# SCH_CubeSat_Arduino__2024-08-11.net
KiCad netlist of a schematic drawn in EasyEDA
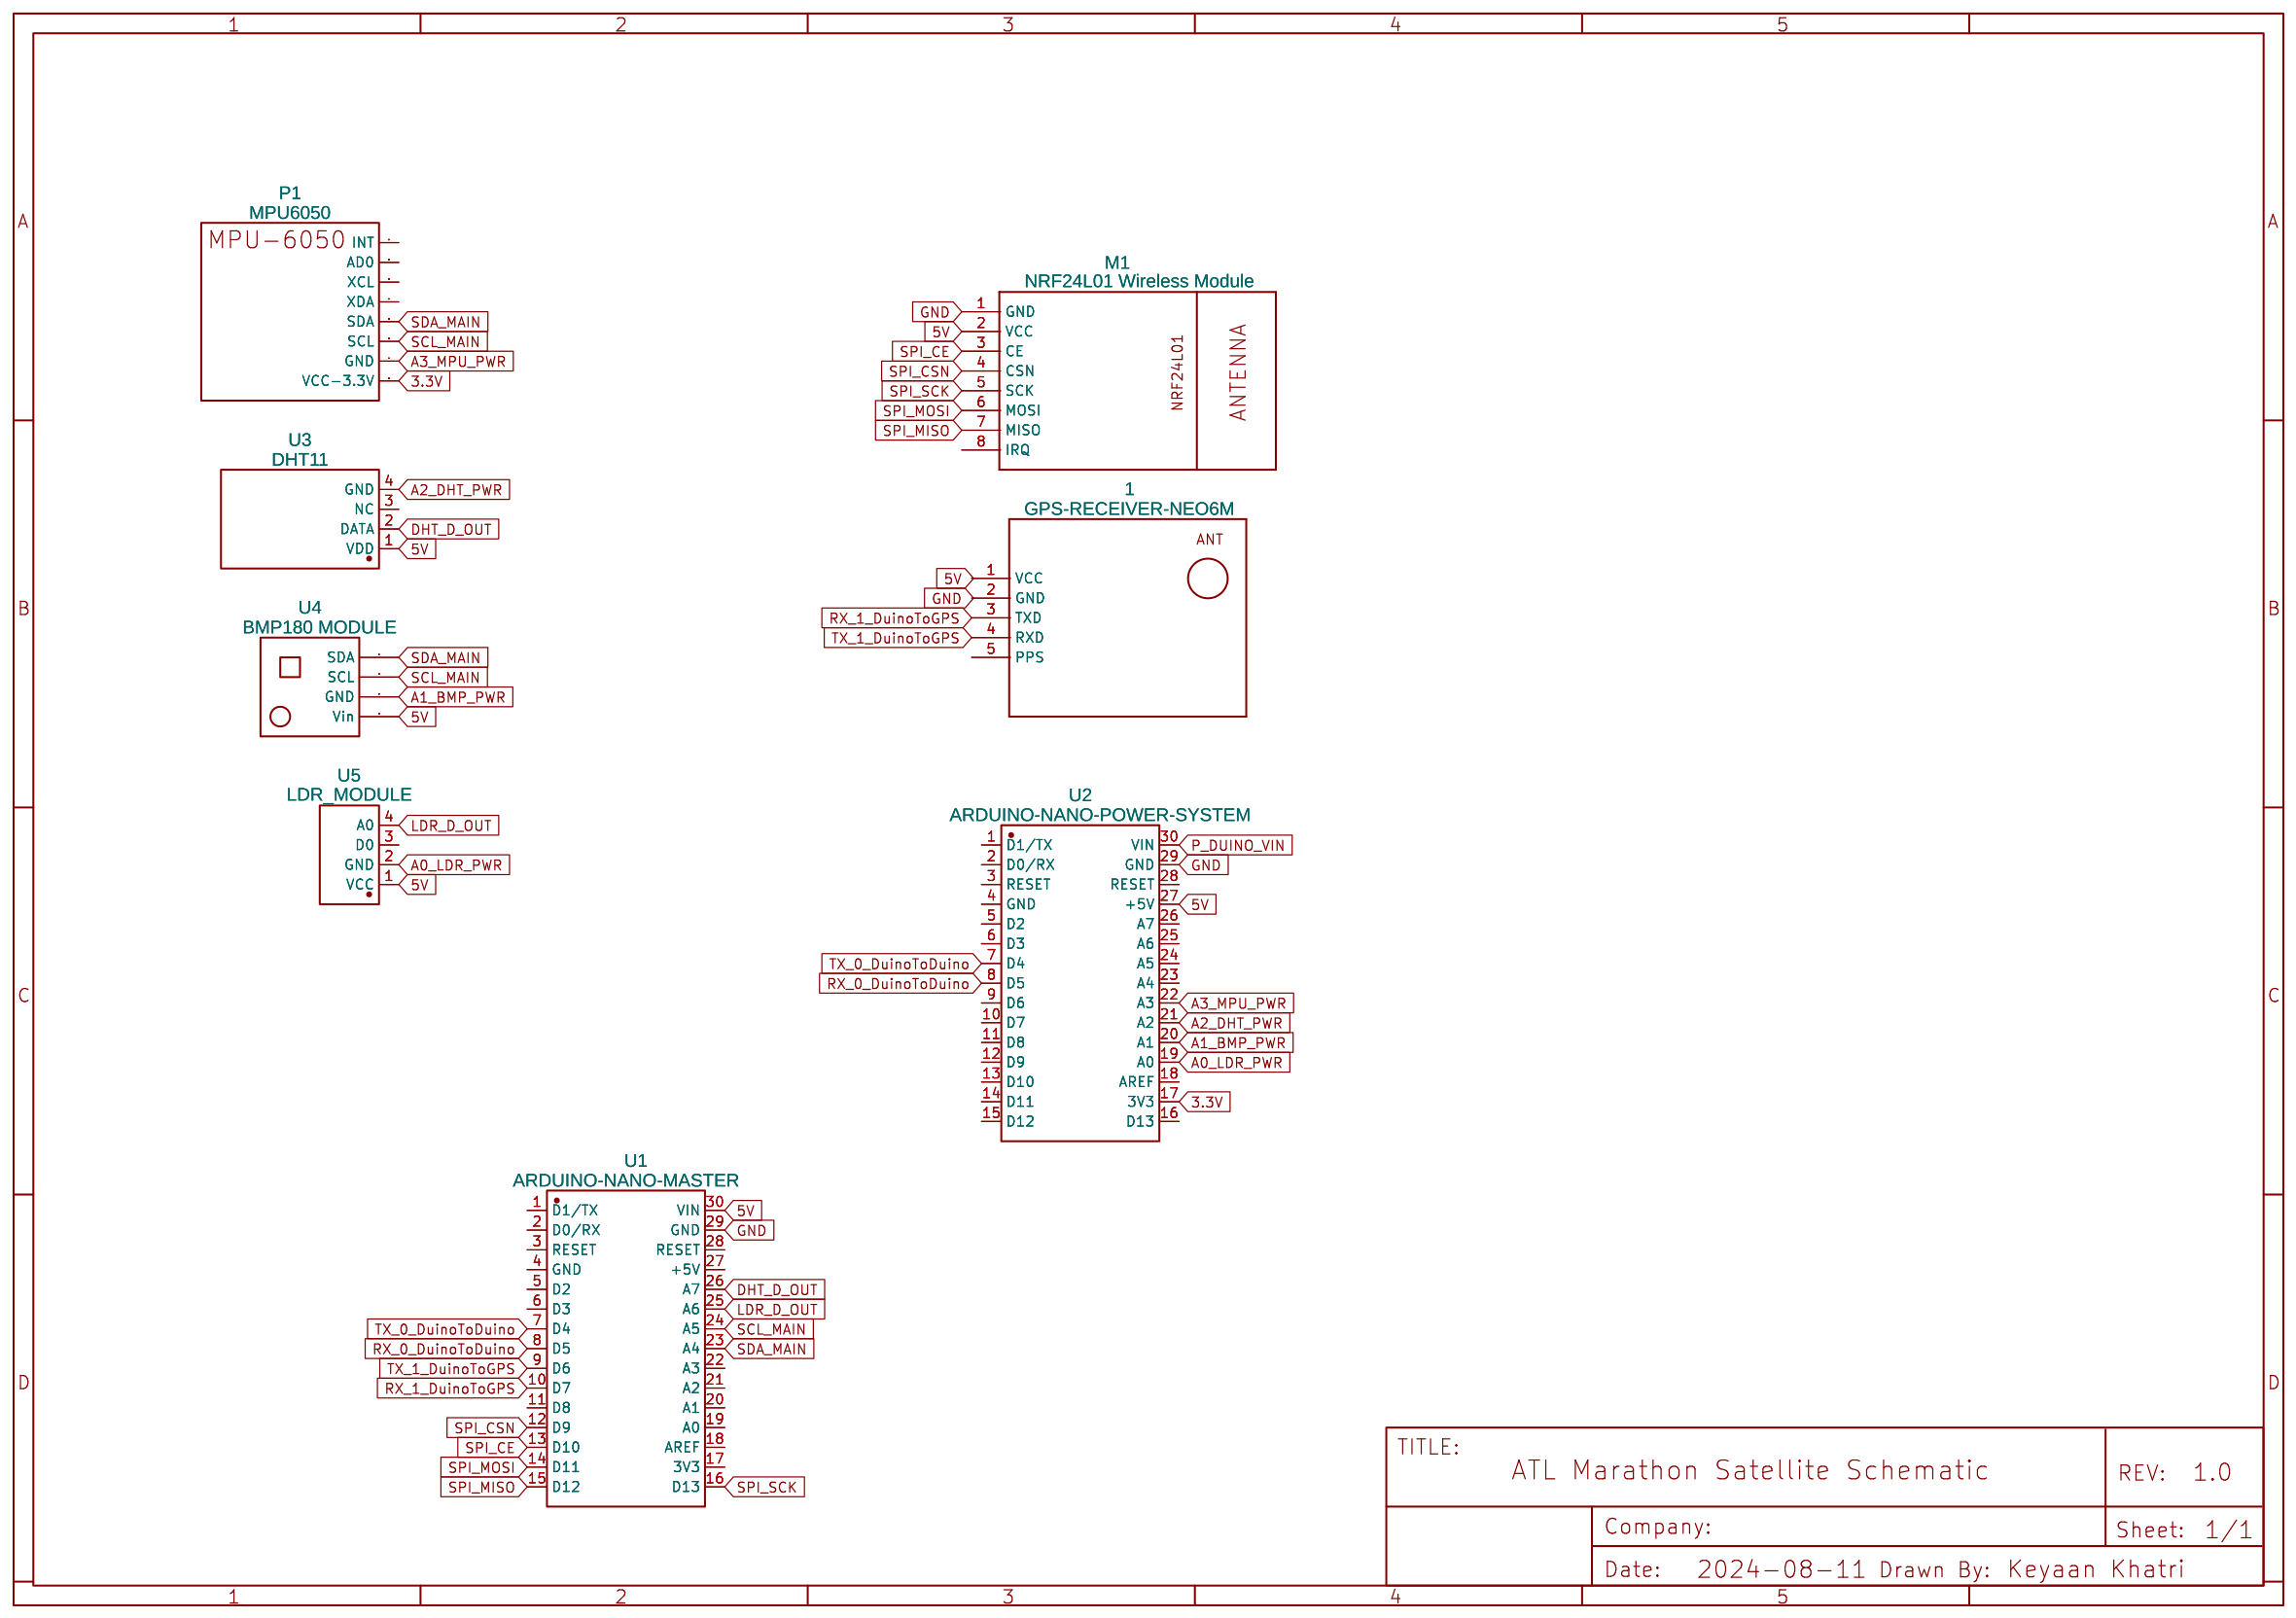
[diagram p0: schematic sheet]

(export (version "E")
  (design (tool "Eeschema 10.0.6"))
  (components
    (comp (ref "1") (value "GPS-RECEIVER-NEO6M") (libsource (lib "") (part "GPS-RECEIVER-NEO6M")))
    (comp (ref "M1")
      (value "NRF24L01 Wireless Module")
      (libsource (lib "") (part "NRF24L01 Wireless Module"))
    )
    (comp (ref "P1")
      (value "MPU6050")
      (fields
        (field (name "Manufacturer Part") "Female headerHDR1X8-2.54")
        (field (name "Manufacturer") "None")
      )
      (libsource (lib "") (part "MPU6050"))
    )
    (comp (ref "U1")
      (value "ARDUINO-NANO-MASTER")
      (fields (field (name "Manufacturer Part") "ARDUINO_NANO"))
      (libsource (lib "") (part "ARDUINO_NANO"))
    )
    (comp (ref "U2")
      (value "ARDUINO-NANO-POWER-SYSTEM")
      (fields (field (name "Manufacturer Part") "ARDUINO_NANO"))
      (libsource (lib "") (part "ARDUINO_NANO"))
    )
    (comp (ref "U3")
      (value "DHT11")
      (fields (field (name "Manufacturer") "广州奥松"))
      (libsource (lib "") (part "DHT11"))
    )
    (comp (ref "U4")
      (value "BMP180 MODULE")
      (fields (field (name "Manufacturer Part") "BMP180 (HW-596)"))
      (libsource (lib "") (part "BMP180 MODULE"))
    )
    (comp (ref "U5") (value "LDR_MODULE") (libsource (lib "") (part "LDR_MODULE")))
  )
  (nets
    (net (code "1") (name "3.3V") (class "Default")
      (node (ref "P1") (pin "8") (pinfunction "VCC-3.3V_8") (pintype "input"))
      (node (ref "U2") (pin "17") (pinfunction "3V3_17") (pintype "unspecified"))
    )
    (net (code "2") (name "5V") (class "Default")
      (node (ref "M1") (pin "2") (pinfunction "VCC_2") (pintype "bidirectional"))
      (node (ref "U1") (pin "30") (pinfunction "VIN_30") (pintype "unspecified"))
      (node (ref "U2") (pin "27") (pinfunction "+5V_27") (pintype "unspecified"))
      (node (ref "U3") (pin "1") (pinfunction "VDD_1") (pintype "unspecified"))
      (node (ref "U4") (pin "1") (pinfunction "Vin_1") (pintype "unspecified"))
      (node (ref "U5") (pin "1") (pinfunction "VCC_1") (pintype "unspecified"))
    )
    (net (code "3") (name "A0_LDR_PWR") (class "Default")
      (node (ref "U2") (pin "19") (pinfunction "A0_19") (pintype "unspecified"))
      (node (ref "U5") (pin "2") (pinfunction "GND_2") (pintype "unspecified"))
    )
    (net (code "4") (name "A1_BMP_PWR") (class "Default")
      (node (ref "U2") (pin "20") (pinfunction "A1_20") (pintype "unspecified"))
      (node (ref "U4") (pin "2") (pinfunction "GND_2") (pintype "unspecified"))
    )
    (net (code "5") (name "A2_DHT_PWR") (class "Default")
      (node (ref "U2") (pin "21") (pinfunction "A2_21") (pintype "unspecified"))
      (node (ref "U3") (pin "4") (pinfunction "GND_4") (pintype "unspecified"))
    )
    (net (code "6") (name "A3_MPU_PWR") (class "Default")
      (node (ref "P1") (pin "7") (pinfunction "GND_7") (pintype "input"))
      (node (ref "U2") (pin "22") (pinfunction "A3_22") (pintype "unspecified"))
    )
    (net (code "7") (name "DHT_D_OUT") (class "Default")
      (node (ref "U1") (pin "26") (pinfunction "A7_26") (pintype "unspecified"))
      (node (ref "U3") (pin "2") (pinfunction "DATA_2") (pintype "unspecified"))
    )
    (net (code "8") (name "GND") (class "Default")
      (node (ref "M1") (pin "1") (pinfunction "GND_1") (pintype "bidirectional"))
      (node (ref "U1") (pin "29") (pinfunction "GND_29") (pintype "unspecified"))
      (node (ref "U2") (pin "29") (pinfunction "GND_29") (pintype "unspecified"))
    )
    (net (code "9") (name "LDR_D_OUT") (class "Default")
      (node (ref "U1") (pin "25") (pinfunction "A6_25") (pintype "unspecified"))
      (node (ref "U5") (pin "4") (pinfunction "A0_4") (pintype "unspecified"))
    )
    (net (code "10") (name "P_DUINO_VIN") (class "Default")
      (node (ref "U2") (pin "30") (pinfunction "VIN_30") (pintype "unspecified"))
    )
    (net (code "11") (name "RX_0_DuinoToDuino") (class "Default")
      (node (ref "U1") (pin "8") (pinfunction "D5_8") (pintype "unspecified"))
      (node (ref "U2") (pin "8") (pinfunction "D5_8") (pintype "unspecified"))
    )
    (net (code "12") (name "RX_1_DuinoToGPS") (class "Default")
      (node (ref "1") (pin "3") (pinfunction "TXD_3") (pintype "bidirectional"))
      (node (ref "U1") (pin "10") (pinfunction "D7_10") (pintype "unspecified"))
    )
    (net (code "13") (name "SCL_MAIN") (class "Default")
      (node (ref "P1") (pin "6") (pinfunction "SCL_6") (pintype "input"))
      (node (ref "U1") (pin "24") (pinfunction "A5_24") (pintype "unspecified"))
      (node (ref "U4") (pin "3") (pinfunction "SCL_3") (pintype "unspecified"))
    )
    (net (code "14") (name "SDA_MAIN") (class "Default")
      (node (ref "P1") (pin "5") (pinfunction "SDA_5") (pintype "input"))
      (node (ref "U1") (pin "23") (pinfunction "A4_23") (pintype "unspecified"))
      (node (ref "U4") (pin "4") (pinfunction "SDA_4") (pintype "unspecified"))
    )
    (net (code "15") (name "SPI_CE") (class "Default")
      (node (ref "M1") (pin "3") (pinfunction "CE_3") (pintype "bidirectional"))
      (node (ref "U1") (pin "13") (pinfunction "D10_13") (pintype "unspecified"))
    )
    (net (code "16") (name "SPI_CSN") (class "Default")
      (node (ref "M1") (pin "4") (pinfunction "CSN_4") (pintype "bidirectional"))
      (node (ref "U1") (pin "12") (pinfunction "D9_12") (pintype "unspecified"))
    )
    (net (code "17") (name "SPI_MISO") (class "Default")
      (node (ref "M1") (pin "7") (pinfunction "MISO_7") (pintype "bidirectional"))
      (node (ref "U1") (pin "15") (pinfunction "D12_15") (pintype "unspecified"))
    )
    (net (code "18") (name "SPI_MOSI") (class "Default")
      (node (ref "M1") (pin "6") (pinfunction "MOSI_6") (pintype "bidirectional"))
      (node (ref "U1") (pin "14") (pinfunction "D11_14") (pintype "unspecified"))
    )
    (net (code "19") (name "SPI_SCK") (class "Default")
      (node (ref "M1") (pin "5") (pinfunction "SCK_5") (pintype "bidirectional"))
      (node (ref "U1") (pin "16") (pinfunction "D13_16") (pintype "unspecified"))
    )
    (net (code "20") (name "TX_0_DuinoToDuino") (class "Default")
      (node (ref "U1") (pin "7") (pinfunction "D4_7") (pintype "unspecified"))
      (node (ref "U2") (pin "7") (pinfunction "D4_7") (pintype "unspecified"))
    )
    (net (code "21") (name "TX_1_DuinoToGPS") (class "Default")
      (node (ref "1") (pin "4") (pinfunction "RXD_4") (pintype "bidirectional"))
      (node (ref "U1") (pin "9") (pinfunction "D6_9") (pintype "unspecified"))
    )
    (net (code "22") (name "unconnected-(1-GND-Pad2)") (class "Default")
      (node (ref "1") (pin "2") (pinfunction "GND_2") (pintype "bidirectional"))
    )
    (net (code "23") (name "unconnected-(1-PPS-Pad5)") (class "Default")
      (node (ref "1") (pin "5") (pinfunction "PPS_5") (pintype "bidirectional"))
    )
    (net (code "24") (name "unconnected-(1-VCC-Pad1)") (class "Default")
      (node (ref "1") (pin "1") (pinfunction "VCC_1") (pintype "bidirectional"))
    )
    (net (code "25") (name "unconnected-(M1-IRQ-Pad8)") (class "Default")
      (node (ref "M1") (pin "8") (pinfunction "IRQ_8") (pintype "bidirectional"))
    )
    (net (code "26") (name "unconnected-(P1-AD0-Pad2)") (class "Default")
      (node (ref "P1") (pin "2") (pinfunction "AD0_2") (pintype "input"))
    )
    (net (code "27") (name "unconnected-(P1-INT-Pad1)") (class "Default")
      (node (ref "P1") (pin "1") (pinfunction "INT_1") (pintype "input"))
    )
    (net (code "28") (name "unconnected-(P1-XCL-Pad3)") (class "Default")
      (node (ref "P1") (pin "3") (pinfunction "XCL_3") (pintype "input"))
    )
    (net (code "29") (name "unconnected-(P1-XDA-Pad4)") (class "Default")
      (node (ref "P1") (pin "4") (pinfunction "XDA_4") (pintype "input"))
    )
    (net (code "30") (name "unconnected-(U1-+5V-Pad27)") (class "Default")
      (node (ref "U1") (pin "27") (pinfunction "+5V_27") (pintype "unspecified"))
    )
    (net (code "31") (name "unconnected-(U1-3V3-Pad17)") (class "Default")
      (node (ref "U1") (pin "17") (pinfunction "3V3_17") (pintype "unspecified"))
    )
    (net (code "32") (name "unconnected-(U1-A0-Pad19)") (class "Default")
      (node (ref "U1") (pin "19") (pinfunction "A0_19") (pintype "unspecified"))
    )
    (net (code "33") (name "unconnected-(U1-A1-Pad20)") (class "Default")
      (node (ref "U1") (pin "20") (pinfunction "A1_20") (pintype "unspecified"))
    )
    (net (code "34") (name "unconnected-(U1-A2-Pad21)") (class "Default")
      (node (ref "U1") (pin "21") (pinfunction "A2_21") (pintype "unspecified"))
    )
    (net (code "35") (name "unconnected-(U1-A3-Pad22)") (class "Default")
      (node (ref "U1") (pin "22") (pinfunction "A3_22") (pintype "unspecified"))
    )
    (net (code "36") (name "unconnected-(U1-AREF-Pad18)") (class "Default")
      (node (ref "U1") (pin "18") (pinfunction "AREF_18") (pintype "unspecified"))
    )
    (net (code "37") (name "unconnected-(U1-D0{slash}RX-Pad2)") (class "Default")
      (node (ref "U1") (pin "2") (pinfunction "D0/RX_2") (pintype "unspecified"))
    )
    (net (code "38") (name "unconnected-(U1-D1{slash}TX-Pad1)") (class "Default")
      (node (ref "U1") (pin "1") (pinfunction "D1/TX_1") (pintype "unspecified"))
    )
    (net (code "39") (name "unconnected-(U1-D2-Pad5)") (class "Default")
      (node (ref "U1") (pin "5") (pinfunction "D2_5") (pintype "unspecified"))
    )
    (net (code "40") (name "unconnected-(U1-D3-Pad6)") (class "Default")
      (node (ref "U1") (pin "6") (pinfunction "D3_6") (pintype "unspecified"))
    )
    (net (code "41") (name "unconnected-(U1-D8-Pad11)") (class "Default")
      (node (ref "U1") (pin "11") (pinfunction "D8_11") (pintype "unspecified"))
    )
    (net (code "42") (name "unconnected-(U1-GND-Pad4)") (class "Default")
      (node (ref "U1") (pin "4") (pinfunction "GND_4") (pintype "unspecified"))
    )
    (net (code "43") (name "unconnected-(U1-RESET-Pad3)") (class "Default")
      (node (ref "U1") (pin "3") (pinfunction "RESET_3") (pintype "unspecified"))
    )
    (net (code "44") (name "unconnected-(U1-RESET-Pad28)") (class "Default")
      (node (ref "U1") (pin "28") (pinfunction "RESET_28") (pintype "unspecified"))
    )
    (net (code "45") (name "unconnected-(U2-A4-Pad23)") (class "Default")
      (node (ref "U2") (pin "23") (pinfunction "A4_23") (pintype "unspecified"))
    )
    (net (code "46") (name "unconnected-(U2-A5-Pad24)") (class "Default")
      (node (ref "U2") (pin "24") (pinfunction "A5_24") (pintype "unspecified"))
    )
    (net (code "47") (name "unconnected-(U2-A6-Pad25)") (class "Default")
      (node (ref "U2") (pin "25") (pinfunction "A6_25") (pintype "unspecified"))
    )
    (net (code "48") (name "unconnected-(U2-A7-Pad26)") (class "Default")
      (node (ref "U2") (pin "26") (pinfunction "A7_26") (pintype "unspecified"))
    )
    (net (code "49") (name "unconnected-(U2-AREF-Pad18)") (class "Default")
      (node (ref "U2") (pin "18") (pinfunction "AREF_18") (pintype "unspecified"))
    )
    (net (code "50") (name "unconnected-(U2-D0{slash}RX-Pad2)") (class "Default")
      (node (ref "U2") (pin "2") (pinfunction "D0/RX_2") (pintype "unspecified"))
    )
    (net (code "51") (name "unconnected-(U2-D1{slash}TX-Pad1)") (class "Default")
      (node (ref "U2") (pin "1") (pinfunction "D1/TX_1") (pintype "unspecified"))
    )
    (net (code "52") (name "unconnected-(U2-D2-Pad5)") (class "Default")
      (node (ref "U2") (pin "5") (pinfunction "D2_5") (pintype "unspecified"))
    )
    (net (code "53") (name "unconnected-(U2-D3-Pad6)") (class "Default")
      (node (ref "U2") (pin "6") (pinfunction "D3_6") (pintype "unspecified"))
    )
    (net (code "54") (name "unconnected-(U2-D6-Pad9)") (class "Default")
      (node (ref "U2") (pin "9") (pinfunction "D6_9") (pintype "unspecified"))
    )
    (net (code "55") (name "unconnected-(U2-D7-Pad10)") (class "Default")
      (node (ref "U2") (pin "10") (pinfunction "D7_10") (pintype "unspecified"))
    )
    (net (code "56") (name "unconnected-(U2-D8-Pad11)") (class "Default")
      (node (ref "U2") (pin "11") (pinfunction "D8_11") (pintype "unspecified"))
    )
    (net (code "57") (name "unconnected-(U2-D9-Pad12)") (class "Default")
      (node (ref "U2") (pin "12") (pinfunction "D9_12") (pintype "unspecified"))
    )
    (net (code "58") (name "unconnected-(U2-D10-Pad13)") (class "Default")
      (node (ref "U2") (pin "13") (pinfunction "D10_13") (pintype "unspecified"))
    )
    (net (code "59") (name "unconnected-(U2-D11-Pad14)") (class "Default")
      (node (ref "U2") (pin "14") (pinfunction "D11_14") (pintype "unspecified"))
    )
    (net (code "60") (name "unconnected-(U2-D12-Pad15)") (class "Default")
      (node (ref "U2") (pin "15") (pinfunction "D12_15") (pintype "unspecified"))
    )
    (net (code "61") (name "unconnected-(U2-D13-Pad16)") (class "Default")
      (node (ref "U2") (pin "16") (pinfunction "D13_16") (pintype "unspecified"))
    )
    (net (code "62") (name "unconnected-(U2-GND-Pad4)") (class "Default")
      (node (ref "U2") (pin "4") (pinfunction "GND_4") (pintype "unspecified"))
    )
    (net (code "63") (name "unconnected-(U2-RESET-Pad3)") (class "Default")
      (node (ref "U2") (pin "3") (pinfunction "RESET_3") (pintype "unspecified"))
    )
    (net (code "64") (name "unconnected-(U2-RESET-Pad28)") (class "Default")
      (node (ref "U2") (pin "28") (pinfunction "RESET_28") (pintype "unspecified"))
    )
    (net (code "65") (name "unconnected-(U3-NC-Pad3)") (class "Default")
      (node (ref "U3") (pin "3") (pinfunction "NC_3") (pintype "unspecified"))
    )
    (net (code "66") (name "unconnected-(U5-D0-Pad3)") (class "Default")
      (node (ref "U5") (pin "3") (pinfunction "D0_3") (pintype "unspecified"))
    )
  )
)
